# BLE-LORA-Relay-30dbm-v2_0.net
KiCad netlist of a schematic drawn in EAGLE
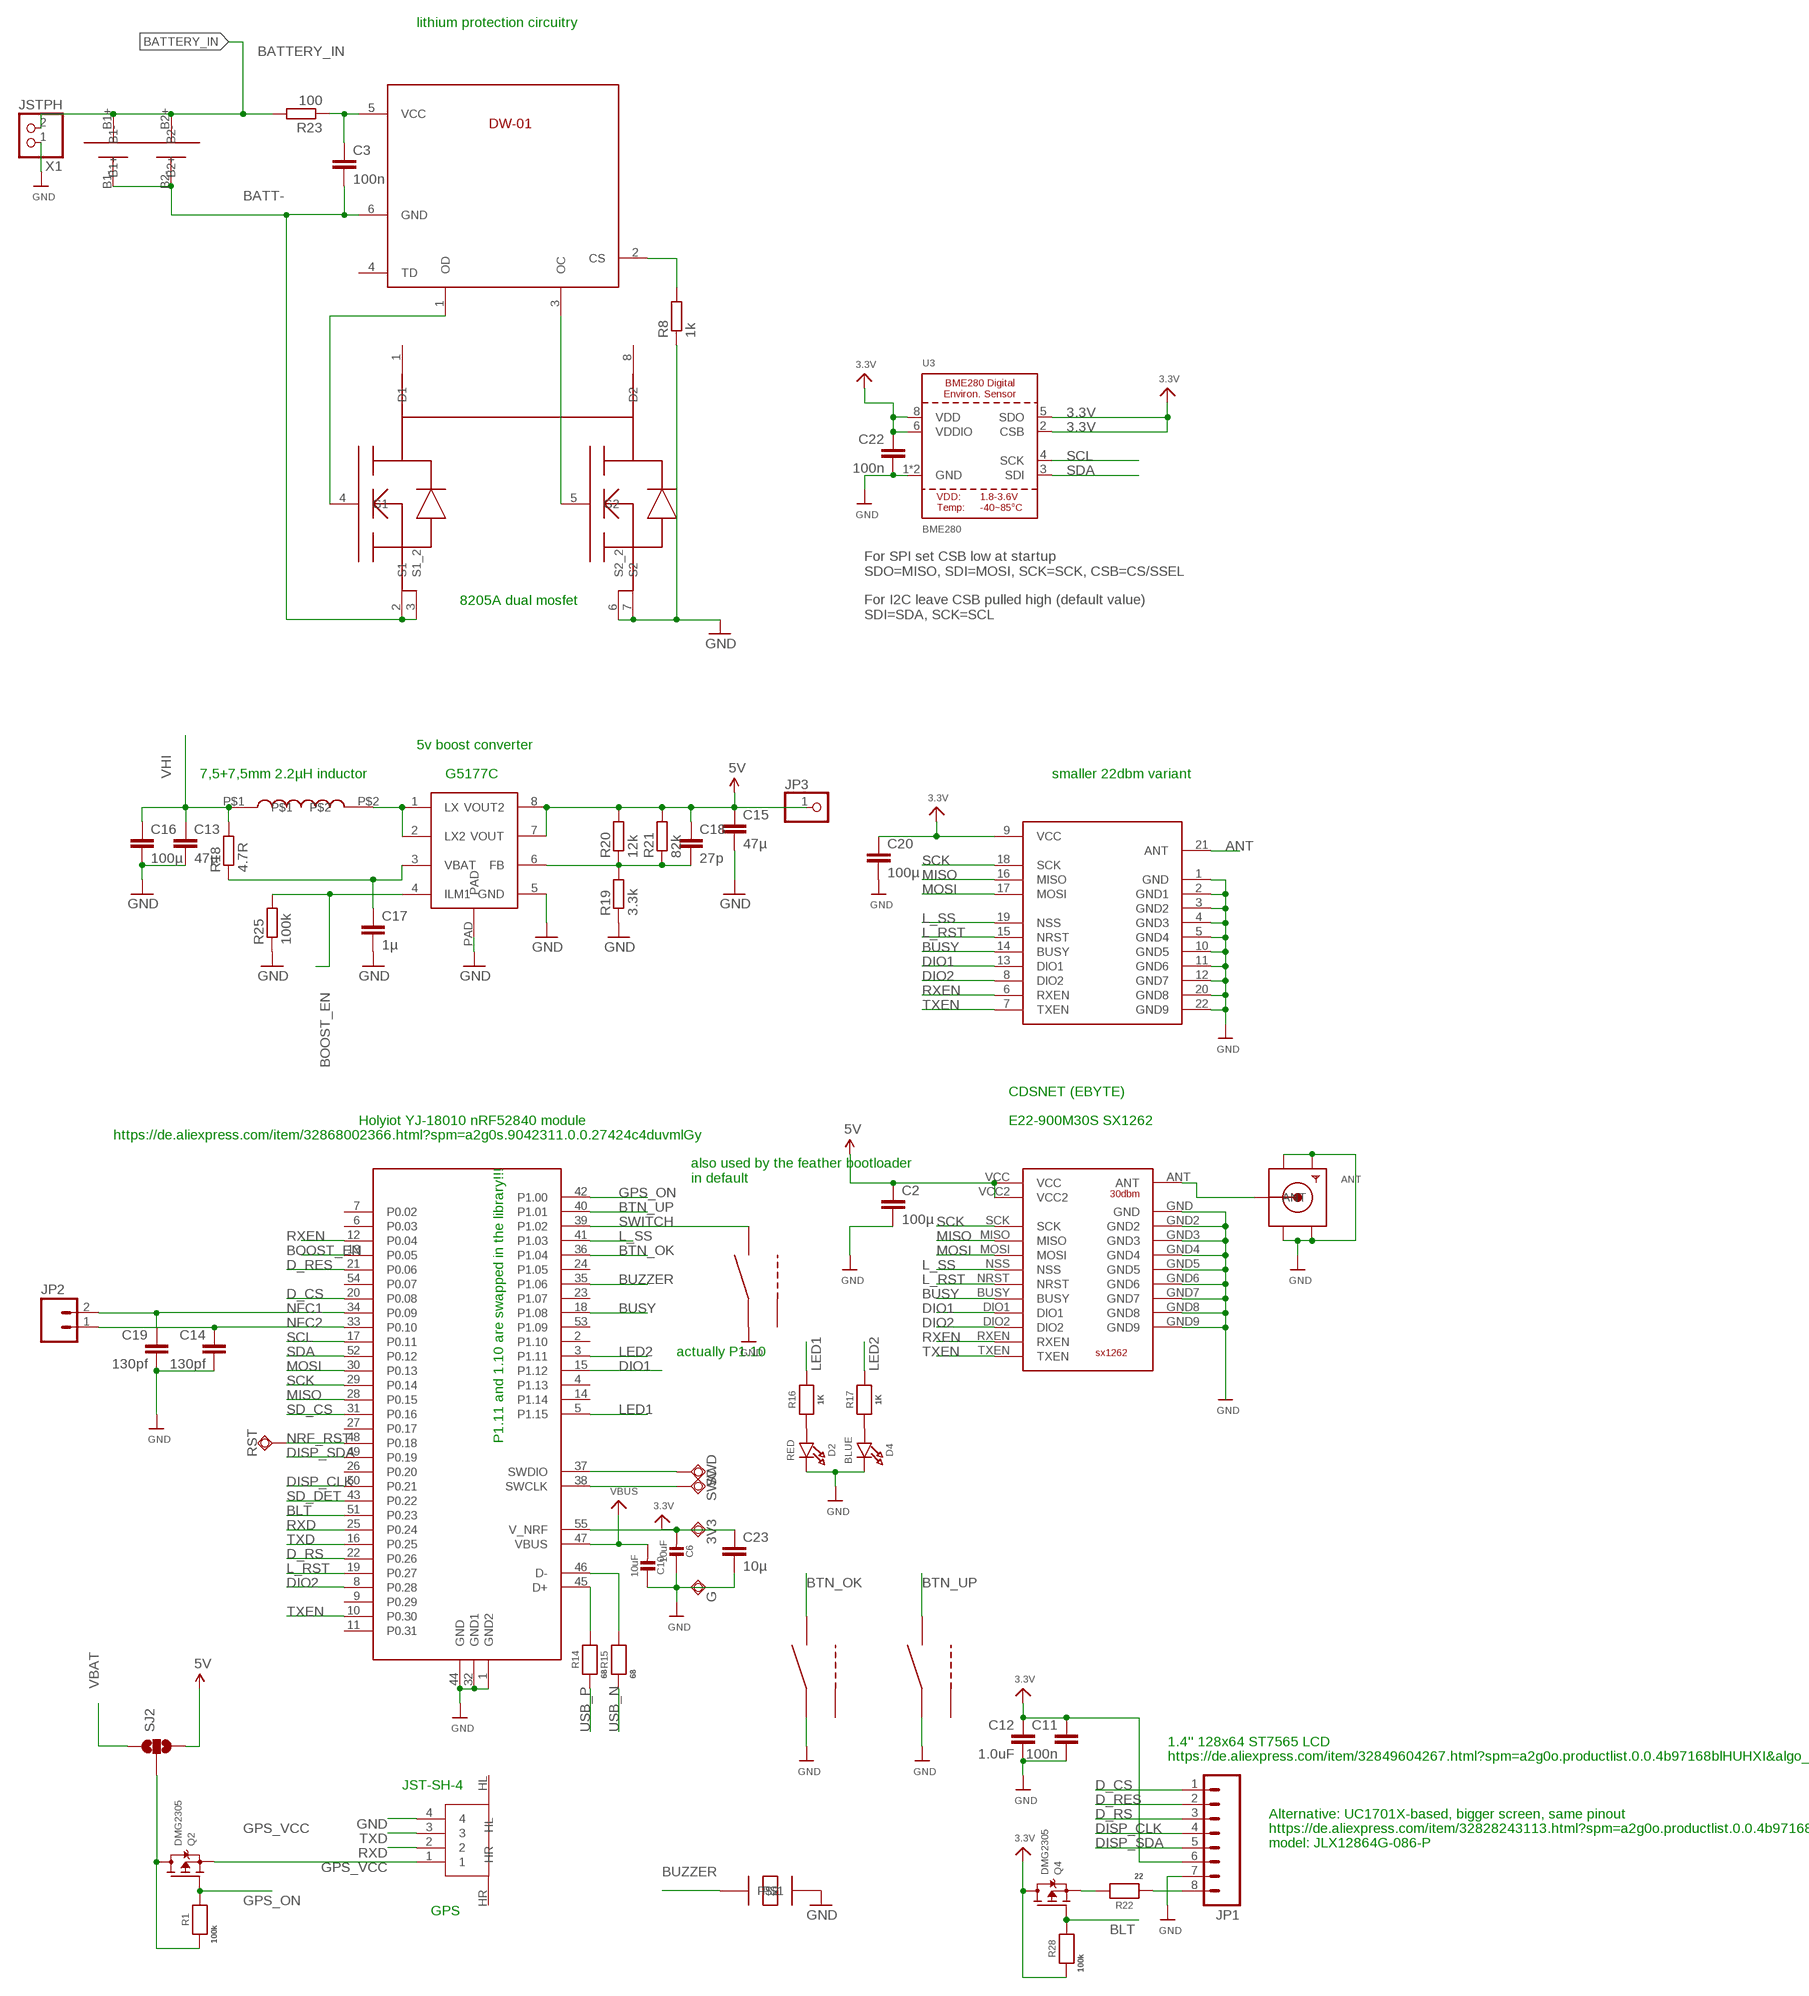
[diagram p0: schematic, sheet 1, part 1 of 3]
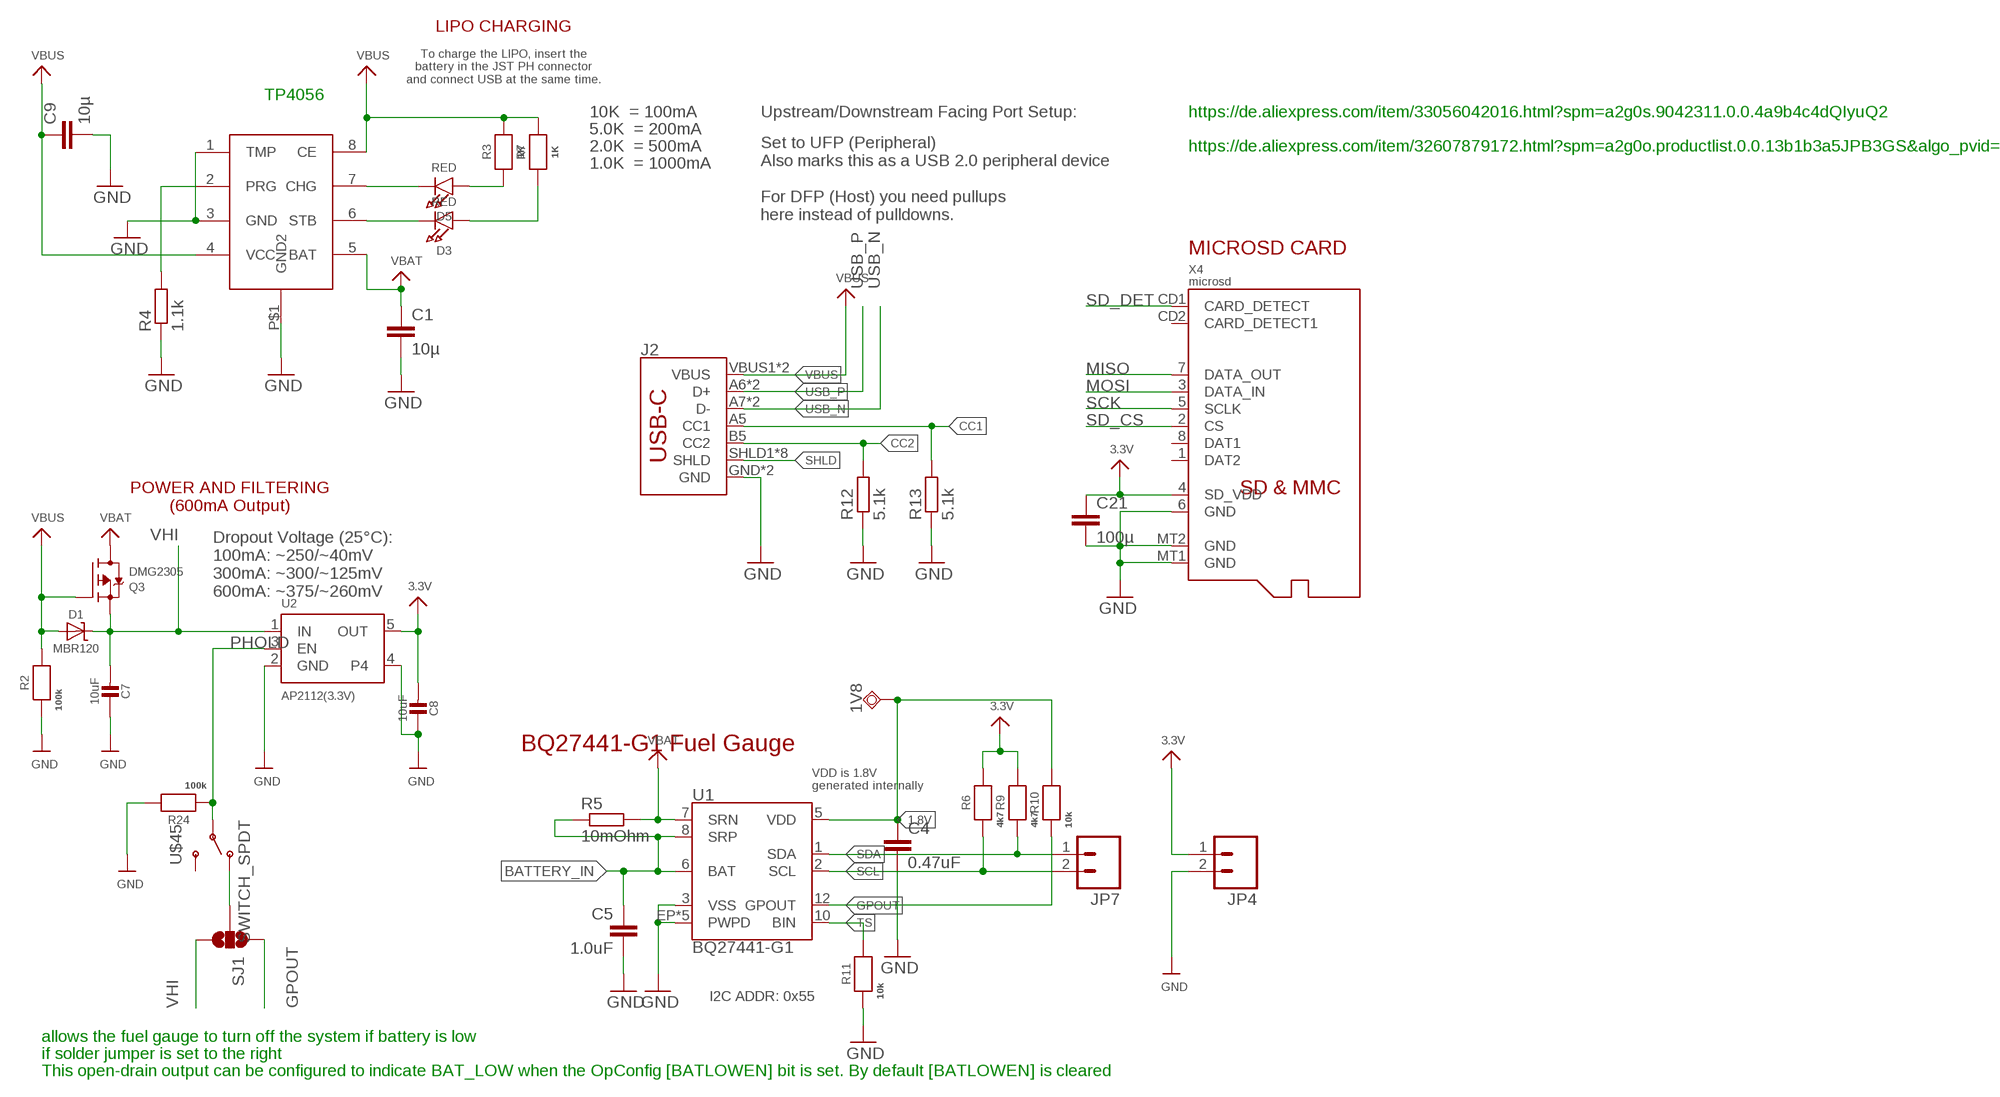
[diagram p1: schematic, sheet 1, part 2 of 3]
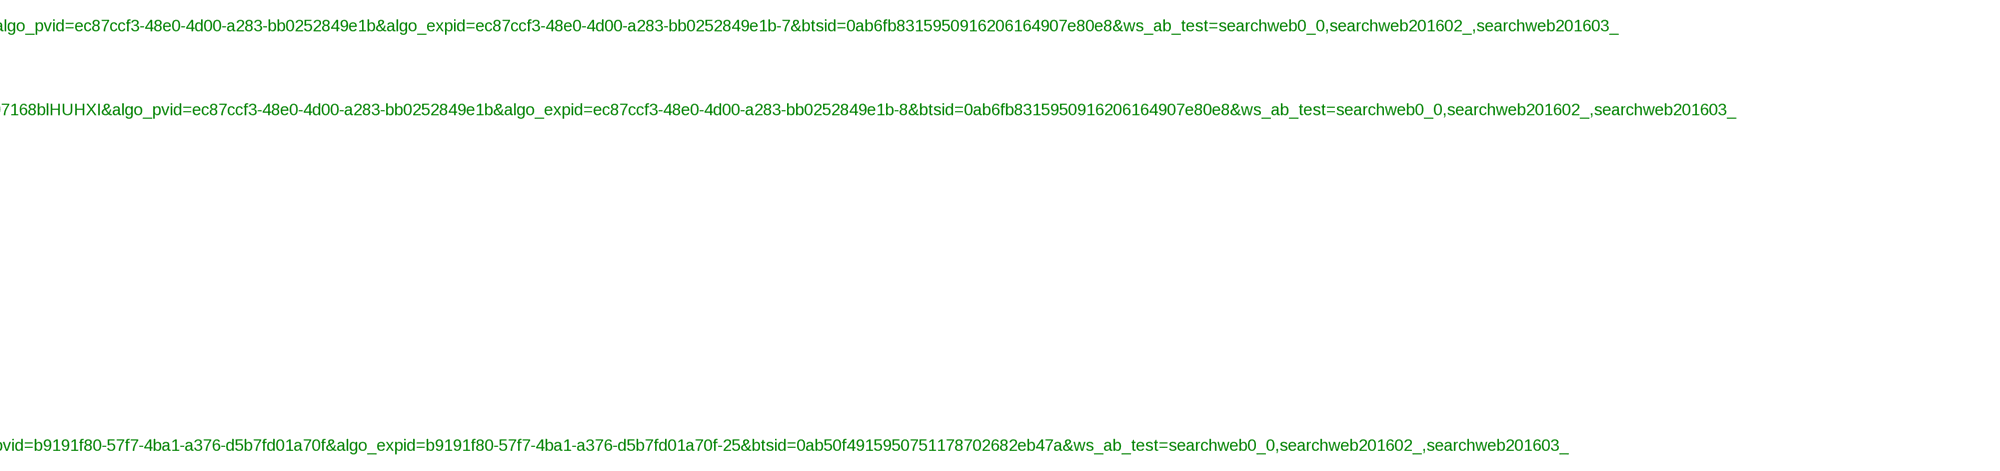
[diagram p2: schematic, sheet 1, part 3 of 3]

(export (version "E")
  (design (tool "Eeschema 10.0.6"))
  (components
    (comp (ref "1V8")
      (value "TPSQTP13R")
      (footprint "eagle-import:TP13R")
      (libsource (lib "eagle-import") (part "TPSQTP13R"))
    )
    (comp (ref "3V3")
      (value "TPSQTP13R")
      (footprint "eagle-import:TP13R")
      (libsource (lib "eagle-import") (part "TPSQTP13R"))
    )
    (comp (ref "ANT")
      (value "SMACONNECTOR_EDGE")
      (footprint "eagle-import:SMA_EDGELAUNCH")
      (libsource (lib "eagle-import") (part "SMACONNECTOR_EDGE"))
    )
    (comp (ref "C1")
      (value "10µ")
      (footprint "eagle-import:C0805")
      (libsource (lib "eagle-import") (part "C-EUC0805"))
    )
    (comp (ref "C2")
      (value "100µ")
      (footprint "eagle-import:C1206")
      (libsource (lib "eagle-import") (part "C-EUC1206"))
    )
    (comp (ref "C3")
      (value "100n")
      (footprint "eagle-import:C0603")
      (libsource (lib "eagle-import") (part "C-EUC0603"))
    )
    (comp (ref "C4")
      (value "0.47uF")
      (footprint "eagle-import:0603-CAP")
      (libsource (lib "eagle-import") (part "CAP0603-CAP"))
    )
    (comp (ref "C5")
      (value "1.0uF")
      (footprint "eagle-import:0603-CAP")
      (libsource (lib "eagle-import") (part "1.0UF-16V-10%(0603)"))
    )
    (comp (ref "C6")
      (value "10uF")
      (footprint "eagle-import:0805-NO")
      (libsource (lib "eagle-import") (part "CAP_CERAMIC0805-NOOUTLINE"))
    )
    (comp (ref "C7")
      (value "10uF")
      (footprint "eagle-import:0805-NO")
      (libsource (lib "eagle-import") (part "CAP_CERAMIC0805-NOOUTLINE"))
    )
    (comp (ref "C8")
      (value "10uF")
      (footprint "eagle-import:0805-NO")
      (libsource (lib "eagle-import") (part "CAP_CERAMIC0805-NOOUTLINE"))
    )
    (comp (ref "C9")
      (value "10µ")
      (footprint "eagle-import:C0805")
      (libsource (lib "eagle-import") (part "C-EUC0805"))
    )
    (comp (ref "C10")
      (value "10uF")
      (footprint "eagle-import:0805-NO")
      (libsource (lib "eagle-import") (part "CAP_CERAMIC0805-NOOUTLINE"))
    )
    (comp (ref "C11")
      (value "100n")
      (footprint "eagle-import:0603-CAP")
      (libsource (lib "eagle-import") (part "1.0UF-16V-10%(0603)"))
    )
    (comp (ref "C12")
      (value "1.0uF")
      (footprint "eagle-import:0603-CAP")
      (libsource (lib "eagle-import") (part "1.0UF-16V-10%(0603)"))
    )
    (comp (ref "C13")
      (value "47µ")
      (footprint "eagle-import:C0805")
      (libsource (lib "eagle-import") (part "C-EUC0805"))
    )
    (comp (ref "C14")
      (value "130pf")
      (footprint "eagle-import:0603-CAP")
      (libsource (lib "eagle-import") (part "1.0UF-16V-10%(0603)"))
    )
    (comp (ref "C15")
      (value "47µ")
      (footprint "eagle-import:C0805")
      (libsource (lib "eagle-import") (part "C-EUC0805"))
    )
    (comp (ref "C16")
      (value "100µ")
      (footprint "eagle-import:C1206")
      (libsource (lib "eagle-import") (part "C-EUC1206"))
    )
    (comp (ref "C17")
      (value "1µ")
      (footprint "eagle-import:C0603")
      (libsource (lib "eagle-import") (part "C-EUC0603"))
    )
    (comp (ref "C18")
      (value "27p")
      (footprint "eagle-import:C0603")
      (libsource (lib "eagle-import") (part "C-EUC0603"))
    )
    (comp (ref "C19")
      (value "130pf")
      (footprint "eagle-import:0603-CAP")
      (libsource (lib "eagle-import") (part "1.0UF-16V-10%(0603)"))
    )
    (comp (ref "C20")
      (value "100µ")
      (footprint "eagle-import:C1206")
      (libsource (lib "eagle-import") (part "C-EUC1206"))
    )
    (comp (ref "C21")
      (value "100µ")
      (footprint "eagle-import:C1206")
      (libsource (lib "eagle-import") (part "C-EUC1206"))
    )
    (comp (ref "C22")
      (value "100n")
      (footprint "eagle-import:0603-CAP")
      (libsource (lib "eagle-import") (part "1.0UF-16V-10%(0603)"))
    )
    (comp (ref "C23")
      (value "10µ")
      (footprint "eagle-import:C0805")
      (libsource (lib "eagle-import") (part "C-EUC0805"))
    )
    (comp (ref "D1")
      (value "MBR120")
      (footprint "eagle-import:SOD-123")
      (libsource (lib "eagle-import") (part "DIODE-SCHOTTKYSOD-123"))
    )
    (comp (ref "D2")
      (value "RED")
      (footprint "eagle-import:CHIPLED_0805_NOOUTLINE")
      (libsource (lib "eagle-import") (part "LED0805_NOOUTLINE"))
    )
    (comp (ref "D3")
      (value "RED")
      (footprint "eagle-import:CHIPLED_0805_NOOUTLINE")
      (libsource (lib "eagle-import") (part "LED0805_NOOUTLINE"))
    )
    (comp (ref "D4")
      (value "BLUE")
      (footprint "eagle-import:CHIPLED_0805_NOOUTLINE")
      (libsource (lib "eagle-import") (part "LED0805_NOOUTLINE"))
    )
    (comp (ref "D5")
      (value "RED")
      (footprint "eagle-import:CHIPLED_0805_NOOUTLINE")
      (libsource (lib "eagle-import") (part "LED0805_NOOUTLINE"))
    )
    (comp (ref "DWN")
      (value "LS12T2")
      (footprint "eagle-import:LS12T2")
      (libsource (lib "eagle-import") (part "LS12T2"))
    )
    (comp (ref "DWN1")
      (value "LS12T2")
      (footprint "eagle-import:LS12T2")
      (libsource (lib "eagle-import") (part "LS12T2"))
    )
    (comp (ref "DWN2")
      (value "LS12T2")
      (footprint "eagle-import:LS12T2")
      (libsource (lib "eagle-import") (part "LS12T2"))
    )
    (comp (ref "G")
      (value "TPSQTP13R")
      (footprint "eagle-import:TP13R")
      (libsource (lib "eagle-import") (part "TPSQTP13R"))
    )
    (comp (ref "J2")
      (value "USB_C16PIN")
      (footprint "eagle-import:USB-C-16P")
      (libsource (lib "eagle-import") (part "USB_C16PIN"))
    )
    (comp (ref "JP1")
      (value "M08")
      (footprint "eagle-import:1X08_ROUND")
      (libsource (lib "eagle-import") (part "M08"))
    )
    (comp (ref "JP2")
      (value "M02PTH")
      (footprint "eagle-import:1X02")
      (libsource (lib "eagle-import") (part "M02PTH"))
    )
    (comp (ref "JP3")
      (value "PINHD-1X1")
      (footprint "eagle-import:1X01")
      (libsource (lib "eagle-import") (part "PINHD-1X1"))
    )
    (comp (ref "JP4")
      (value "M02PTH")
      (footprint "eagle-import:1X02")
      (libsource (lib "eagle-import") (part "M02PTH"))
    )
    (comp (ref "JP7")
      (value "M02PTH")
      (footprint "eagle-import:1X02")
      (libsource (lib "eagle-import") (part "M02PTH"))
    )
    (comp (ref "Q2")
      (value "DMG2305")
      (footprint "eagle-import:SOT23-R")
      (libsource (lib "eagle-import") (part "MOSFET-P"))
    )
    (comp (ref "Q3")
      (value "DMG2305")
      (footprint "eagle-import:SOT23-R")
      (libsource (lib "eagle-import") (part "MOSFET-P"))
    )
    (comp (ref "Q4")
      (value "DMG2305")
      (footprint "eagle-import:SOT23-R")
      (libsource (lib "eagle-import") (part "MOSFET-P"))
    )
    (comp (ref "R1")
      (value "100k")
      (footprint "eagle-import:0603-NO")
      (libsource (lib "eagle-import") (part "RESISTOR_0603_NOOUT"))
    )
    (comp (ref "R2")
      (value "100k")
      (footprint "eagle-import:0603-NO")
      (libsource (lib "eagle-import") (part "RESISTOR_0603_NOOUT"))
    )
    (comp (ref "R3")
      (value "1K")
      (footprint "eagle-import:0603-NO")
      (libsource (lib "eagle-import") (part "RESISTOR_0603_NOOUT"))
    )
    (comp (ref "R4")
      (value "1.1k")
      (footprint "eagle-import:R0603")
      (libsource (lib "eagle-import") (part "R-EU_R0603"))
    )
    (comp (ref "R5")
      (value "10mOhm")
      (footprint "eagle-import:R0805")
      (libsource (lib "eagle-import") (part "R-EU_R0805"))
    )
    (comp (ref "R6")
      (value "4k7")
      (footprint "eagle-import:0603-NO")
      (libsource (lib "eagle-import") (part "RESISTOR_0603_NOOUT"))
    )
    (comp (ref "R7")
      (value "1K")
      (footprint "eagle-import:0603-NO")
      (libsource (lib "eagle-import") (part "RESISTOR_0603_NOOUT"))
    )
    (comp (ref "R8")
      (value "1k")
      (footprint "eagle-import:R0603")
      (libsource (lib "eagle-import") (part "R-EU_R0603"))
    )
    (comp (ref "R9")
      (value "4k7")
      (footprint "eagle-import:0603-NO")
      (libsource (lib "eagle-import") (part "RESISTOR_0603_NOOUT"))
    )
    (comp (ref "R10")
      (value "10k")
      (footprint "eagle-import:0603-NO")
      (libsource (lib "eagle-import") (part "RESISTOR_0603_NOOUT"))
    )
    (comp (ref "R11")
      (value "10k")
      (footprint "eagle-import:0603-NO")
      (libsource (lib "eagle-import") (part "RESISTOR_0603_NOOUT"))
    )
    (comp (ref "R12")
      (value "5.1k")
      (footprint "eagle-import:R0603")
      (libsource (lib "eagle-import") (part "R-EU_R0603"))
    )
    (comp (ref "R13")
      (value "5.1k")
      (footprint "eagle-import:R0603")
      (libsource (lib "eagle-import") (part "R-EU_R0603"))
    )
    (comp (ref "R14")
      (value "68")
      (footprint "eagle-import:0603-NO")
      (libsource (lib "eagle-import") (part "RESISTOR_0603_NOOUT"))
    )
    (comp (ref "R15")
      (value "68")
      (footprint "eagle-import:0603-NO")
      (libsource (lib "eagle-import") (part "RESISTOR_0603_NOOUT"))
    )
    (comp (ref "R16")
      (value "1K")
      (footprint "eagle-import:0603-NO")
      (libsource (lib "eagle-import") (part "RESISTOR_0603_NOOUT"))
    )
    (comp (ref "R17")
      (value "1K")
      (footprint "eagle-import:0603-NO")
      (libsource (lib "eagle-import") (part "RESISTOR_0603_NOOUT"))
    )
    (comp (ref "R18")
      (value "4.7R")
      (footprint "eagle-import:R0603")
      (libsource (lib "eagle-import") (part "R-EU_R0603"))
    )
    (comp (ref "R19")
      (value "3.3k")
      (footprint "eagle-import:R0603")
      (libsource (lib "eagle-import") (part "R-EU_R0603"))
    )
    (comp (ref "R20")
      (value "12k")
      (footprint "eagle-import:R0603")
      (libsource (lib "eagle-import") (part "R-EU_R0603"))
    )
    (comp (ref "R21")
      (value "82k")
      (footprint "eagle-import:R0603")
      (libsource (lib "eagle-import") (part "R-EU_R0603"))
    )
    (comp (ref "R22")
      (value "22")
      (footprint "eagle-import:0603-NO")
      (libsource (lib "eagle-import") (part "RESISTOR_0603_NOOUT"))
    )
    (comp (ref "R23")
      (value "100")
      (footprint "eagle-import:R0603")
      (libsource (lib "eagle-import") (part "R-EU_R0603"))
    )
    (comp (ref "R24")
      (value "100k")
      (footprint "eagle-import:0603-NO")
      (libsource (lib "eagle-import") (part "RESISTOR_0603_NOOUT"))
    )
    (comp (ref "R25")
      (value "100k")
      (footprint "eagle-import:R0603")
      (libsource (lib "eagle-import") (part "R-EU_R0603"))
    )
    (comp (ref "R28")
      (value "100k")
      (footprint "eagle-import:0603-NO")
      (libsource (lib "eagle-import") (part "RESISTOR_0603_NOOUT"))
    )
    (comp (ref "RST")
      (value "TPSQTP13R")
      (footprint "eagle-import:TP13R")
      (libsource (lib "eagle-import") (part "TPSQTP13R"))
    )
    (comp (ref "SJ1")
      (value "SOLDERJUMPER_2WAY-OLDS")
      (footprint "eagle-import:SJ_3")
      (libsource (lib "eagle-import") (part "SOLDERJUMPER_2WAY-OLDS"))
    )
    (comp (ref "SJ2")
      (value "SOLDERJUMPER_2WAY-OLDS")
      (footprint "eagle-import:SJ_3")
      (libsource (lib "eagle-import") (part "SOLDERJUMPER_2WAY-OLDS"))
    )
    (comp (ref "SWC")
      (value "TPSQTP13R")
      (footprint "eagle-import:TP13R")
      (libsource (lib "eagle-import") (part "TPSQTP13R"))
    )
    (comp (ref "SWD")
      (value "TPSQTP13R")
      (footprint "eagle-import:TP13R")
      (libsource (lib "eagle-import") (part "TPSQTP13R"))
    )
    (comp (ref "U$2")
      (value "BUZZER")
      (footprint "eagle-import:BUZZER")
      (libsource (lib "eagle-import") (part "BUZZER"))
    )
    (comp (ref "U$3")
      (value "TP4056")
      (footprint "eagle-import:SO-08")
      (libsource (lib "eagle-import") (part "TP4056"))
    )
    (comp (ref "U$10")
      (value "2X18650")
      (footprint "eagle-import:2X18650")
      (libsource (lib "eagle-import") (part "2X18650"))
    )
    (comp (ref "U$14")
      (value "NRF52840")
      (footprint "eagle-import:NRF52840MOD")
      (libsource (lib "eagle-import") (part "NRF52840"))
    )
    (comp (ref "U$15")
      (value "SX1262-30DBM")
      (footprint "eagle-import:SX1262-30DBM")
      (libsource (lib "eagle-import") (part "SX1262-30DBM"))
    )
    (comp (ref "U$17")
      (value "JST-SH-3")
      (footprint "eagle-import:JST-SH-3")
      (libsource (lib "eagle-import") (part "JST-SH-3"))
    )
    (comp (ref "U$35")
      (value "7.5MM-COIL")
      (footprint "eagle-import:7.5MM_COIL")
      (libsource (lib "eagle-import") (part "7.5MM-COIL"))
    )
    (comp (ref "U$36")
      (value "SX1292-EBYTE")
      (footprint "eagle-import:SX1262_EBYTE")
      (libsource (lib "eagle-import") (part "SX1292-EBYTE"))
    )
    (comp (ref "U$38")
      (value "DW-01")
      (footprint "eagle-import:SOT23-6")
      (libsource (lib "eagle-import") (part "DW-01"))
    )
    (comp (ref "U$41")
      (value "G5177C")
      (footprint "eagle-import:SO-08")
      (libsource (lib "eagle-import") (part "G5177C"))
    )
    (comp (ref "U$45")
      (value "SWITCH_SPDT")
      (footprint "eagle-import:KPS-1290")
      (libsource (lib "eagle-import") (part "SWITCH_SPDT"))
    )
    (comp (ref "U$46")
      (value "8205A")
      (footprint "eagle-import:TSSOP8")
      (libsource (lib "eagle-import") (part "8205A"))
    )
    (comp (ref "U1")
      (value "BQ27441-G1")
      (footprint "eagle-import:PDSO-N12")
      (libsource (lib "eagle-import") (part "BQ27441-G1"))
    )
    (comp (ref "U2")
      (value "AP2112(3.3V)")
      (footprint "eagle-import:SOT23-5")
      (libsource (lib "eagle-import") (part "VREG_SOT23-5"))
    )
    (comp (ref "U3")
      (value "BME280")
      (footprint "eagle-import:BME280")
      (libsource (lib "eagle-import") (part "BME280"))
    )
    (comp (ref "X1")
      (value "JSTPH")
      (footprint "eagle-import:JSTPH2")
      (libsource (lib "eagle-import") (part "CON_JST_PH_2PIN"))
    )
    (comp (ref "X4")
      (value "microsd")
      (footprint "eagle-import:MICROSD")
      (libsource (lib "eagle-import") (part "MICROSD"))
    )
  )
  (nets
    (net (code "1") (name "/ANT") (class "Default")
      (node (ref "ANT") (pin "P") (pinfunction "ANT_P") (pintype "bidirectional"))
      (node (ref "U$15") (pin "ANT") (pinfunction "ANT_ANT") (pintype "bidirectional"))
      (node (ref "U$36") (pin "21") (pinfunction "ANT_21") (pintype "bidirectional"))
    )
    (net (code "2") (name "/BATT-") (class "Default")
      (node (ref "C3") (pin "2") (pinfunction "2_2") (pintype "passive"))
      (node (ref "U$10") (pin "B1-") (pinfunction "B1-_B1-") (pintype "bidirectional"))
      (node (ref "U$10") (pin "B2-") (pinfunction "B2-_B2-") (pintype "bidirectional"))
      (node (ref "U$38") (pin "6") (pinfunction "GND_6") (pintype "bidirectional"))
      (node (ref "U$46") (pin "2") (pinfunction "S1_2") (pintype "bidirectional"))
      (node (ref "U$46") (pin "3") (pinfunction "S1_2_3") (pintype "bidirectional"))
    )
    (net (code "3") (name "/BLT") (class "Default")
      (node (ref "Q4") (pin "1") (pinfunction "G_1") (pintype "passive"))
      (node (ref "R28") (pin "2") (pinfunction "2_2") (pintype "passive"))
      (node (ref "U$14") (pin "51") (pinfunction "P0.23_51") (pintype "bidirectional"))
    )
    (net (code "4") (name "/BOOST_EN") (class "Default")
      (node (ref "R25") (pin "2") (pinfunction "2_2") (pintype "passive"))
      (node (ref "U$14") (pin "13") (pinfunction "P0.05_13") (pintype "bidirectional"))
      (node (ref "U$41") (pin "4") (pinfunction "ILM1_4") (pintype "bidirectional"))
    )
    (net (code "5") (name "/BTN_OK") (class "Default")
      (node (ref "DWN") (pin "1") (pinfunction "1_1") (pintype "bidirectional"))
      (node (ref "U$14") (pin "36") (pinfunction "P1.04_36") (pintype "bidirectional"))
    )
    (net (code "6") (name "/BTN_UP") (class "Default")
      (node (ref "DWN1") (pin "1") (pinfunction "1_1") (pintype "bidirectional"))
      (node (ref "U$14") (pin "40") (pinfunction "P1.01_40") (pintype "bidirectional"))
    )
    (net (code "7") (name "/BUSY") (class "Default")
      (node (ref "U$14") (pin "18") (pinfunction "P1.08_18") (pintype "bidirectional"))
      (node (ref "U$15") (pin "BUSY") (pinfunction "BUSY_BUSY") (pintype "bidirectional"))
      (node (ref "U$36") (pin "14") (pinfunction "BUSY_14") (pintype "bidirectional"))
    )
    (net (code "8") (name "/BUZZER") (class "Default")
      (node (ref "U$14") (pin "35") (pinfunction "P1.06_35") (pintype "bidirectional"))
      (node (ref "U$2") (pin "P$1") (pinfunction "P$1_P$1") (pintype "bidirectional"))
    )
    (net (code "9") (name "/DIO1") (class "Default")
      (node (ref "U$14") (pin "15") (pinfunction "P1.12_15") (pintype "bidirectional"))
      (node (ref "U$15") (pin "DIO1") (pinfunction "DIO1_DIO1") (pintype "bidirectional"))
      (node (ref "U$36") (pin "13") (pinfunction "DIO1_13") (pintype "bidirectional"))
    )
    (net (code "10") (name "/DIO2") (class "Default")
      (node (ref "U$14") (pin "8") (pinfunction "P0.28_8") (pintype "bidirectional"))
      (node (ref "U$15") (pin "DIO2") (pinfunction "DIO2_DIO2") (pintype "bidirectional"))
      (node (ref "U$36") (pin "8") (pinfunction "DIO2_8") (pintype "bidirectional"))
    )
    (net (code "11") (name "/DISP_CLK") (class "Default")
      (node (ref "JP1") (pin "4") (pinfunction "4_4") (pintype "passive"))
      (node (ref "U$14") (pin "50") (pinfunction "P0.21_50") (pintype "bidirectional"))
    )
    (net (code "12") (name "/DISP_SDA") (class "Default")
      (node (ref "JP1") (pin "5") (pinfunction "5_5") (pintype "passive"))
      (node (ref "U$14") (pin "49") (pinfunction "P0.19_49") (pintype "bidirectional"))
    )
    (net (code "13") (name "/D_CS") (class "Default")
      (node (ref "JP1") (pin "1") (pinfunction "1_1") (pintype "passive"))
      (node (ref "U$14") (pin "20") (pinfunction "P0.08_20") (pintype "bidirectional"))
    )
    (net (code "14") (name "/D_RES") (class "Default")
      (node (ref "JP1") (pin "2") (pinfunction "2_2") (pintype "passive"))
      (node (ref "U$14") (pin "21") (pinfunction "P0.06_21") (pintype "bidirectional"))
    )
    (net (code "15") (name "/D_RS") (class "Default")
      (node (ref "JP1") (pin "3") (pinfunction "3_3") (pintype "passive"))
      (node (ref "U$14") (pin "22") (pinfunction "P0.26_22") (pintype "bidirectional"))
    )
    (net (code "16") (name "/GPS_ON") (class "Default")
      (node (ref "Q2") (pin "1") (pinfunction "G_1") (pintype "passive"))
      (node (ref "R1") (pin "2") (pinfunction "2_2") (pintype "passive"))
      (node (ref "U$14") (pin "42") (pinfunction "P1.00_42") (pintype "bidirectional"))
    )
    (net (code "17") (name "/GPS_VCC") (class "Default")
      (node (ref "Q2") (pin "2") (pinfunction "S_2") (pintype "passive"))
      (node (ref "U$17") (pin "1") (pinfunction "1_1") (pintype "bidirectional"))
    )
    (net (code "18") (name "/LED1") (class "Default")
      (node (ref "R16") (pin "2") (pinfunction "2_2") (pintype "passive"))
      (node (ref "U$14") (pin "5") (pinfunction "P1.15_5") (pintype "bidirectional"))
    )
    (net (code "19") (name "/LED2") (class "Default")
      (node (ref "R17") (pin "2") (pinfunction "2_2") (pintype "passive"))
      (node (ref "U$14") (pin "3") (pinfunction "P1.11_3") (pintype "bidirectional"))
    )
    (net (code "20") (name "/L_RST") (class "Default")
      (node (ref "U$14") (pin "19") (pinfunction "P0.27_19") (pintype "bidirectional"))
      (node (ref "U$15") (pin "NRST") (pinfunction "NRST_NRST") (pintype "bidirectional"))
      (node (ref "U$36") (pin "15") (pinfunction "NRST_15") (pintype "bidirectional"))
    )
    (net (code "21") (name "/L_SS") (class "Default")
      (node (ref "U$14") (pin "41") (pinfunction "P1.03_41") (pintype "bidirectional"))
      (node (ref "U$15") (pin "NSS") (pinfunction "NSS_NSS") (pintype "bidirectional"))
      (node (ref "U$36") (pin "19") (pinfunction "NSS_19") (pintype "bidirectional"))
    )
    (net (code "22") (name "/MISO") (class "Default")
      (node (ref "U$14") (pin "28") (pinfunction "P0.15_28") (pintype "bidirectional"))
      (node (ref "U$15") (pin "MISO") (pinfunction "MISO_MISO") (pintype "bidirectional"))
      (node (ref "U$36") (pin "16") (pinfunction "MISO_16") (pintype "bidirectional"))
      (node (ref "X4") (pin "7") (pinfunction "DATA_OUT_7") (pintype "output"))
    )
    (net (code "23") (name "/MOSI") (class "Default")
      (node (ref "U$14") (pin "30") (pinfunction "P0.13_30") (pintype "bidirectional"))
      (node (ref "U$15") (pin "MOSI") (pinfunction "MOSI_MOSI") (pintype "bidirectional"))
      (node (ref "U$36") (pin "17") (pinfunction "MOSI_17") (pintype "bidirectional"))
      (node (ref "X4") (pin "3") (pinfunction "DATA_IN_3") (pintype "input"))
    )
    (net (code "24") (name "/NFC1") (class "Default")
      (node (ref "C19") (pin "1") (pinfunction "1_1") (pintype "passive"))
      (node (ref "JP2") (pin "2") (pinfunction "2_2") (pintype "passive"))
      (node (ref "U$14") (pin "34") (pinfunction "P0.09_34") (pintype "bidirectional"))
    )
    (net (code "25") (name "/NFC2") (class "Default")
      (node (ref "C14") (pin "1") (pinfunction "1_1") (pintype "passive"))
      (node (ref "JP2") (pin "1") (pinfunction "1_1") (pintype "passive"))
      (node (ref "U$14") (pin "33") (pinfunction "P0.10_33") (pintype "bidirectional"))
    )
    (net (code "26") (name "/NRF_RST") (class "Default")
      (node (ref "RST") (pin "TP") (pinfunction "TP_TP") (pintype "input"))
      (node (ref "U$14") (pin "48") (pinfunction "P0.18_48") (pintype "bidirectional"))
    )
    (net (code "27") (name "/PHOLD") (class "Default")
      (node (ref "R24") (pin "1") (pinfunction "1_1") (pintype "passive"))
      (node (ref "U$45") (pin "P") (pinfunction "P_P") (pintype "passive"))
      (node (ref "U2") (pin "3") (pinfunction "EN_3") (pintype "input"))
    )
    (net (code "28") (name "/RXD") (class "Default")
      (node (ref "U$14") (pin "25") (pinfunction "P0.24_25") (pintype "bidirectional"))
      (node (ref "U$17") (pin "2") (pinfunction "2_2") (pintype "bidirectional"))
    )
    (net (code "29") (name "/RXEN") (class "Default")
      (node (ref "U$14") (pin "12") (pinfunction "P0.04_12") (pintype "bidirectional"))
      (node (ref "U$15") (pin "RXEN") (pinfunction "RXEN_RXEN") (pintype "bidirectional"))
      (node (ref "U$36") (pin "6") (pinfunction "RXEN_6") (pintype "bidirectional"))
    )
    (net (code "30") (name "/SCK") (class "Default")
      (node (ref "U$14") (pin "29") (pinfunction "P0.14_29") (pintype "bidirectional"))
      (node (ref "U$15") (pin "SCK") (pinfunction "SCK_SCK") (pintype "bidirectional"))
      (node (ref "U$36") (pin "18") (pinfunction "SCK_18") (pintype "bidirectional"))
      (node (ref "X4") (pin "5") (pinfunction "SCLK_5") (pintype "input"))
    )
    (net (code "31") (name "/SD_CS") (class "Default")
      (node (ref "U$14") (pin "31") (pinfunction "P0.16_31") (pintype "bidirectional"))
      (node (ref "X4") (pin "2") (pinfunction "CS_2") (pintype "input"))
    )
    (net (code "32") (name "/SD_DET") (class "Default")
      (node (ref "U$14") (pin "43") (pinfunction "P0.22_43") (pintype "bidirectional"))
      (node (ref "X4") (pin "CD1") (pinfunction "CARD_DETECT_CD1") (pintype "passive"))
    )
    (net (code "33") (name "/SWITCH") (class "Default")
      (node (ref "DWN2") (pin "1") (pinfunction "1_1") (pintype "bidirectional"))
      (node (ref "U$14") (pin "39") (pinfunction "P1.02_39") (pintype "bidirectional"))
    )
    (net (code "34") (name "/TXD") (class "Default")
      (node (ref "U$14") (pin "16") (pinfunction "P0.25_16") (pintype "bidirectional"))
      (node (ref "U$17") (pin "3") (pinfunction "3_3") (pintype "bidirectional"))
    )
    (net (code "35") (name "/TXEN") (class "Default")
      (node (ref "U$14") (pin "10") (pinfunction "P0.30_10") (pintype "bidirectional"))
      (node (ref "U$15") (pin "TXEN") (pinfunction "TXEN_TXEN") (pintype "bidirectional"))
      (node (ref "U$36") (pin "7") (pinfunction "TXEN_7") (pintype "bidirectional"))
    )
    (net (code "36") (name "/VHI") (class "Default")
      (node (ref "C13") (pin "1") (pinfunction "1_1") (pintype "passive"))
      (node (ref "C16") (pin "1") (pinfunction "1_1") (pintype "passive"))
      (node (ref "C7") (pin "2") (pinfunction "2_2") (pintype "passive"))
      (node (ref "D1") (pin "C") (pinfunction "C_C") (pintype "passive"))
      (node (ref "Q3") (pin "2") (pinfunction "S_2") (pintype "passive"))
      (node (ref "R18") (pin "2") (pinfunction "2_2") (pintype "passive"))
      (node (ref "SJ1") (pin "3") (pinfunction "3_3") (pintype "passive"))
      (node (ref "U$35") (pin "P$1") (pinfunction "P$1_P$1") (pintype "bidirectional"))
      (node (ref "U2") (pin "1") (pinfunction "IN_1") (pintype "power_in"))
    )
    (net (code "37") (name "1.8V") (class "Default")
      (node (ref "1V8") (pin "TP") (pinfunction "TP_TP") (pintype "input"))
      (node (ref "C4") (pin "1") (pinfunction "1_1") (pintype "passive"))
      (node (ref "R10") (pin "2") (pinfunction "2_2") (pintype "passive"))
      (node (ref "U1") (pin "5") (pinfunction "VDD_5") (pintype "bidirectional"))
    )
    (net (code "38") (name "3.3V") (class "Default")
      (node (ref "3V3") (pin "TP") (pinfunction "TP_TP") (pintype "input"))
      (node (ref "C11") (pin "1") (pinfunction "1_1") (pintype "passive"))
      (node (ref "C12") (pin "1") (pinfunction "1_1") (pintype "passive"))
      (node (ref "C20") (pin "1") (pinfunction "1_1") (pintype "passive"))
      (node (ref "C21") (pin "1") (pinfunction "1_1") (pintype "passive"))
      (node (ref "C22") (pin "1") (pinfunction "1_1") (pintype "passive"))
      (node (ref "C23") (pin "1") (pinfunction "1_1") (pintype "passive"))
      (node (ref "C6") (pin "2") (pinfunction "2_2") (pintype "passive"))
      (node (ref "C8") (pin "2") (pinfunction "2_2") (pintype "passive"))
      (node (ref "JP1") (pin "6") (pinfunction "6_6") (pintype "passive"))
      (node (ref "JP4") (pin "1") (pinfunction "1_1") (pintype "passive"))
      (node (ref "Q4") (pin "3") (pinfunction "D_3") (pintype "passive"))
      (node (ref "R28") (pin "1") (pinfunction "1_1") (pintype "passive"))
      (node (ref "R6") (pin "2") (pinfunction "2_2") (pintype "passive"))
      (node (ref "R9") (pin "2") (pinfunction "2_2") (pintype "passive"))
      (node (ref "U$14") (pin "55") (pinfunction "V_NRF_55") (pintype "bidirectional"))
      (node (ref "U$36") (pin "9") (pinfunction "VCC_9") (pintype "bidirectional"))
      (node (ref "U2") (pin "5") (pinfunction "OUT_5") (pintype "power_in"))
      (node (ref "U3") (pin "2") (pinfunction "CSB_2") (pintype "input"))
      (node (ref "U3") (pin "5") (pinfunction "SDO_5") (pintype "output"))
      (node (ref "U3") (pin "6") (pinfunction "VDDIO_6") (pintype "power_in"))
      (node (ref "U3") (pin "8") (pinfunction "VDD_8") (pintype "power_in"))
      (node (ref "X4") (pin "4") (pinfunction "SD_VDD_4") (pintype "power_in"))
    )
    (net (code "39") (name "5V") (class "Default")
      (node (ref "C15") (pin "1") (pinfunction "1_1") (pintype "passive"))
      (node (ref "C18") (pin "1") (pinfunction "1_1") (pintype "passive"))
      (node (ref "C2") (pin "1") (pinfunction "1_1") (pintype "passive"))
      (node (ref "JP3") (pin "1") (pinfunction "1_1") (pintype "passive"))
      (node (ref "R20") (pin "2") (pinfunction "2_2") (pintype "passive"))
      (node (ref "R21") (pin "2") (pinfunction "2_2") (pintype "passive"))
      (node (ref "SJ2") (pin "3") (pinfunction "3_3") (pintype "passive"))
      (node (ref "U$15") (pin "VCC") (pinfunction "VCC_VCC") (pintype "bidirectional"))
      (node (ref "U$15") (pin "VCC2") (pinfunction "VCC2_VCC2") (pintype "bidirectional"))
      (node (ref "U$41") (pin "7") (pinfunction "VOUT_7") (pintype "bidirectional"))
      (node (ref "U$41") (pin "8") (pinfunction "VOUT2_8") (pintype "bidirectional"))
    )
    (net (code "40") (name "BATTERY_IN") (class "Default")
      (node (ref "C5") (pin "1") (pinfunction "1_1") (pintype "passive"))
      (node (ref "R23") (pin "2") (pinfunction "2_2") (pintype "passive"))
      (node (ref "R5") (pin "1") (pinfunction "1_1") (pintype "passive"))
      (node (ref "U$10") (pin "B1+") (pinfunction "B1+_B1+") (pintype "bidirectional"))
      (node (ref "U$10") (pin "B2+") (pinfunction "B2+_B2+") (pintype "bidirectional"))
      (node (ref "U1") (pin "6") (pinfunction "BAT_6") (pintype "bidirectional"))
      (node (ref "U1") (pin "8") (pinfunction "SRP_8") (pintype "bidirectional"))
      (node (ref "X1") (pin "2") (pinfunction "2_2") (pintype "passive"))
    )
    (net (code "41") (name "CC1") (class "Default")
      (node (ref "J2") (pin "A5") (pinfunction "CC1_A5") (pintype "bidirectional"))
      (node (ref "R13") (pin "2") (pinfunction "2_2") (pintype "passive"))
    )
    (net (code "42") (name "CC2") (class "Default")
      (node (ref "J2") (pin "B5") (pinfunction "CC2_B5") (pintype "bidirectional"))
      (node (ref "R12") (pin "2") (pinfunction "2_2") (pintype "passive"))
    )
    (net (code "43") (name "GND") (class "Default")
      (node (ref "ANT") (pin "GND@1") (pinfunction "GND4_GND@1") (pintype "power_in"))
      (node (ref "ANT") (pin "GND@2") (pinfunction "GND3_GND@2") (pintype "power_in"))
      (node (ref "ANT") (pin "GND@3") (pinfunction "GND2_GND@3") (pintype "power_in"))
      (node (ref "ANT") (pin "GND@4") (pinfunction "GND1_GND@4") (pintype "power_in"))
      (node (ref "C1") (pin "2") (pinfunction "2_2") (pintype "passive"))
      (node (ref "C10") (pin "1") (pinfunction "1_1") (pintype "passive"))
      (node (ref "C11") (pin "2") (pinfunction "2_2") (pintype "passive"))
      (node (ref "C12") (pin "2") (pinfunction "2_2") (pintype "passive"))
      (node (ref "C13") (pin "2") (pinfunction "2_2") (pintype "passive"))
      (node (ref "C14") (pin "2") (pinfunction "2_2") (pintype "passive"))
      (node (ref "C15") (pin "2") (pinfunction "2_2") (pintype "passive"))
      (node (ref "C16") (pin "2") (pinfunction "2_2") (pintype "passive"))
      (node (ref "C17") (pin "2") (pinfunction "2_2") (pintype "passive"))
      (node (ref "C19") (pin "2") (pinfunction "2_2") (pintype "passive"))
      (node (ref "C2") (pin "2") (pinfunction "2_2") (pintype "passive"))
      (node (ref "C20") (pin "2") (pinfunction "2_2") (pintype "passive"))
      (node (ref "C21") (pin "2") (pinfunction "2_2") (pintype "passive"))
      (node (ref "C22") (pin "2") (pinfunction "2_2") (pintype "passive"))
      (node (ref "C23") (pin "2") (pinfunction "2_2") (pintype "passive"))
      (node (ref "C4") (pin "2") (pinfunction "2_2") (pintype "passive"))
      (node (ref "C5") (pin "2") (pinfunction "2_2") (pintype "passive"))
      (node (ref "C6") (pin "1") (pinfunction "1_1") (pintype "passive"))
      (node (ref "C7") (pin "1") (pinfunction "1_1") (pintype "passive"))
      (node (ref "C8") (pin "1") (pinfunction "1_1") (pintype "passive"))
      (node (ref "C9") (pin "2") (pinfunction "2_2") (pintype "passive"))
      (node (ref "D2") (pin "C") (pinfunction "C_C") (pintype "passive"))
      (node (ref "D4") (pin "C") (pinfunction "C_C") (pintype "passive"))
      (node (ref "DWN") (pin "2") (pinfunction "2_2") (pintype "bidirectional"))
      (node (ref "DWN1") (pin "2") (pinfunction "2_2") (pintype "bidirectional"))
      (node (ref "DWN2") (pin "2") (pinfunction "2_2") (pintype "bidirectional"))
      (node (ref "G") (pin "TP") (pinfunction "TP_TP") (pintype "input"))
      (node (ref "J2") (pin "GND") (pinfunction "GND_GND") (pintype "bidirectional"))
      (node (ref "J2") (pin "GND2") (pinfunction "GND_GND2") (pintype "bidirectional"))
      (node (ref "JP1") (pin "7") (pinfunction "7_7") (pintype "passive"))
      (node (ref "JP4") (pin "2") (pinfunction "2_2") (pintype "passive"))
      (node (ref "R11") (pin "1") (pinfunction "1_1") (pintype "passive"))
      (node (ref "R12") (pin "1") (pinfunction "1_1") (pintype "passive"))
      (node (ref "R13") (pin "1") (pinfunction "1_1") (pintype "passive"))
      (node (ref "R19") (pin "1") (pinfunction "1_1") (pintype "passive"))
      (node (ref "R2") (pin "1") (pinfunction "1_1") (pintype "passive"))
      (node (ref "R24") (pin "2") (pinfunction "2_2") (pintype "passive"))
      (node (ref "R25") (pin "1") (pinfunction "1_1") (pintype "passive"))
      (node (ref "R4") (pin "1") (pinfunction "1_1") (pintype "passive"))
      (node (ref "R8") (pin "1") (pinfunction "1_1") (pintype "passive"))
      (node (ref "U$14") (pin "1") (pinfunction "GND2_1") (pintype "bidirectional"))
      (node (ref "U$14") (pin "32") (pinfunction "GND1_32") (pintype "bidirectional"))
      (node (ref "U$14") (pin "44") (pinfunction "GND_44") (pintype "bidirectional"))
      (node (ref "U$15") (pin "GND") (pinfunction "GND_GND") (pintype "bidirectional"))
      (node (ref "U$15") (pin "GND2") (pinfunction "GND2_GND2") (pintype "bidirectional"))
      (node (ref "U$15") (pin "GND3") (pinfunction "GND3_GND3") (pintype "bidirectional"))
      (node (ref "U$15") (pin "GND4") (pinfunction "GND4_GND4") (pintype "bidirectional"))
      (node (ref "U$15") (pin "GND5") (pinfunction "GND5_GND5") (pintype "bidirectional"))
      (node (ref "U$15") (pin "GND6") (pinfunction "GND6_GND6") (pintype "bidirectional"))
      (node (ref "U$15") (pin "GND7") (pinfunction "GND7_GND7") (pintype "bidirectional"))
      (node (ref "U$15") (pin "GND8") (pinfunction "GND8_GND8") (pintype "bidirectional"))
      (node (ref "U$15") (pin "GND9") (pinfunction "GND9_GND9") (pintype "bidirectional"))
      (node (ref "U$17") (pin "4") (pinfunction "4_4") (pintype "bidirectional"))
      (node (ref "U$2") (pin "P$2") (pinfunction "P$2_P$2") (pintype "bidirectional"))
      (node (ref "U$3") (pin "1") (pinfunction "TMP_1") (pintype "bidirectional"))
      (node (ref "U$3") (pin "3") (pinfunction "GND_3") (pintype "bidirectional"))
      (node (ref "U$3") (pin "P$1") (pinfunction "GND2_P$1") (pintype "bidirectional"))
      (node (ref "U$36") (pin "1") (pinfunction "GND_1") (pintype "bidirectional"))
      (node (ref "U$36") (pin "10") (pinfunction "GND5_10") (pintype "bidirectional"))
      (node (ref "U$36") (pin "11") (pinfunction "GND6_11") (pintype "bidirectional"))
      (node (ref "U$36") (pin "12") (pinfunction "GND7_12") (pintype "bidirectional"))
      (node (ref "U$36") (pin "2") (pinfunction "GND1_2") (pintype "bidirectional"))
      (node (ref "U$36") (pin "20") (pinfunction "GND8_20") (pintype "bidirectional"))
      (node (ref "U$36") (pin "22") (pinfunction "GND9_22") (pintype "bidirectional"))
      (node (ref "U$36") (pin "3") (pinfunction "GND2_3") (pintype "bidirectional"))
      (node (ref "U$36") (pin "4") (pinfunction "GND3_4") (pintype "bidirectional"))
      (node (ref "U$36") (pin "5") (pinfunction "GND4_5") (pintype "bidirectional"))
      (node (ref "U$41") (pin "5") (pinfunction "GND_5") (pintype "bidirectional"))
      (node (ref "U$41") (pin "PAD") (pinfunction "PAD_PAD") (pintype "bidirectional"))
      (node (ref "U$46") (pin "6") (pinfunction "S2_2_6") (pintype "bidirectional"))
      (node (ref "U$46") (pin "7") (pinfunction "S2_7") (pintype "bidirectional"))
      (node (ref "U1") (pin "3") (pinfunction "VSS_3") (pintype "bidirectional"))
      (node (ref "U1") (pin "EP") (pinfunction "PWPD_EP") (pintype "bidirectional"))
      (node (ref "U1") (pin "EP1") (pinfunction "PWPD_EP1") (pintype "bidirectional"))
      (node (ref "U1") (pin "EP2") (pinfunction "PWPD_EP2") (pintype "bidirectional"))
      (node (ref "U1") (pin "EP3") (pinfunction "PWPD_EP3") (pintype "bidirectional"))
      (node (ref "U1") (pin "EP4") (pinfunction "PWPD_EP4") (pintype "bidirectional"))
      (node (ref "U2") (pin "2") (pinfunction "GND_2") (pintype "power_in"))
      (node (ref "U2") (pin "4") (pinfunction "P4_4") (pintype "bidirectional"))
      (node (ref "U3") (pin "1") (pinfunction "GND_1") (pintype "power_in"))
      (node (ref "U3") (pin "7") (pinfunction "GND_7") (pintype "power_in"))
      (node (ref "X1") (pin "1") (pinfunction "1_1") (pintype "passive"))
      (node (ref "X4") (pin "6") (pinfunction "GND_6") (pintype "power_in"))
      (node (ref "X4") (pin "MT1") (pinfunction "GND_MT1") (pintype "power_in"))
      (node (ref "X4") (pin "MT2") (pinfunction "GND_MT2") (pintype "power_in"))
    )
    (net (code "44") (name "GPOUT") (class "Default")
      (node (ref "R10") (pin "1") (pinfunction "1_1") (pintype "passive"))
      (node (ref "SJ1") (pin "1") (pinfunction "1_1") (pintype "passive"))
      (node (ref "U1") (pin "12") (pinfunction "GPOUT_12") (pintype "bidirectional"))
    )
    (net (code "45") (name "Net-(D2-PadA)") (class "Default")
      (node (ref "D2") (pin "A") (pinfunction "A_A") (pintype "passive"))
      (node (ref "R16") (pin "1") (pinfunction "1_1") (pintype "passive"))
    )
    (net (code "46") (name "Net-(D3-PadA)") (class "Default")
      (node (ref "D3") (pin "A") (pinfunction "A_A") (pintype "passive"))
      (node (ref "R7") (pin "1") (pinfunction "1_1") (pintype "passive"))
    )
    (net (code "47") (name "Net-(D4-PadA)") (class "Default")
      (node (ref "D4") (pin "A") (pinfunction "A_A") (pintype "passive"))
      (node (ref "R17") (pin "1") (pinfunction "1_1") (pintype "passive"))
    )
    (net (code "48") (name "Net-(D5-PadA)") (class "Default")
      (node (ref "D5") (pin "A") (pinfunction "A_A") (pintype "passive"))
      (node (ref "R3") (pin "1") (pinfunction "1_1") (pintype "passive"))
    )
    (net (code "49") (name "Net-(JP1-Pad8)") (class "Default")
      (node (ref "JP1") (pin "8") (pinfunction "8_8") (pintype "passive"))
      (node (ref "R22") (pin "1") (pinfunction "1_1") (pintype "passive"))
    )
    (net (code "50") (name "Net-(Q2-D)") (class "Default")
      (node (ref "Q2") (pin "3") (pinfunction "D_3") (pintype "passive"))
      (node (ref "R1") (pin "1") (pinfunction "1_1") (pintype "passive"))
      (node (ref "SJ2") (pin "2") (pinfunction "2_2") (pintype "passive"))
    )
    (net (code "51") (name "Net-(Q4-S)") (class "Default")
      (node (ref "Q4") (pin "2") (pinfunction "S_2") (pintype "passive"))
      (node (ref "R22") (pin "2") (pinfunction "2_2") (pintype "passive"))
    )
    (net (code "52") (name "Net-(SJ1-Pad2)") (class "Default")
      (node (ref "SJ1") (pin "2") (pinfunction "2_2") (pintype "passive"))
      (node (ref "U$45") (pin "O") (pinfunction "O_O") (pintype "passive"))
    )
    (net (code "53") (name "Net-(U$3-CHG)") (class "Default")
      (node (ref "D5") (pin "C") (pinfunction "C_C") (pintype "passive"))
      (node (ref "U$3") (pin "7") (pinfunction "CHG_7") (pintype "bidirectional"))
    )
    (net (code "54") (name "Net-(U$3-PRG)") (class "Default")
      (node (ref "R4") (pin "2") (pinfunction "2_2") (pintype "passive"))
      (node (ref "U$3") (pin "2") (pinfunction "PRG_2") (pintype "bidirectional"))
    )
    (net (code "55") (name "Net-(U$3-STB)") (class "Default")
      (node (ref "D3") (pin "C") (pinfunction "C_C") (pintype "passive"))
      (node (ref "U$3") (pin "6") (pinfunction "STB_6") (pintype "bidirectional"))
    )
    (net (code "56") (name "Net-(U$14-D+)") (class "Default")
      (node (ref "R14") (pin "2") (pinfunction "2_2") (pintype "passive"))
      (node (ref "U$14") (pin "45") (pinfunction "D+_45") (pintype "bidirectional"))
    )
    (net (code "57") (name "Net-(U$14-D-)") (class "Default")
      (node (ref "R15") (pin "2") (pinfunction "2_2") (pintype "passive"))
      (node (ref "U$14") (pin "46") (pinfunction "D-_46") (pintype "bidirectional"))
    )
    (net (code "58") (name "Net-(U$14-SWCLK)") (class "Default")
      (node (ref "SWC") (pin "TP") (pinfunction "TP_TP") (pintype "input"))
      (node (ref "U$14") (pin "38") (pinfunction "SWCLK_38") (pintype "bidirectional"))
    )
    (net (code "59") (name "Net-(U$14-SWDIO)") (class "Default")
      (node (ref "SWD") (pin "TP") (pinfunction "TP_TP") (pintype "input"))
      (node (ref "U$14") (pin "37") (pinfunction "SWDIO_37") (pintype "bidirectional"))
    )
    (net (code "60") (name "Net-(U$38-CS)") (class "Default")
      (node (ref "R8") (pin "2") (pinfunction "2_2") (pintype "passive"))
      (node (ref "U$38") (pin "2") (pinfunction "CS_2") (pintype "bidirectional"))
    )
    (net (code "61") (name "Net-(U$38-OC)") (class "Default")
      (node (ref "U$38") (pin "3") (pinfunction "OC_3") (pintype "bidirectional"))
      (node (ref "U$46") (pin "5") (pinfunction "G2_5") (pintype "bidirectional"))
    )
    (net (code "62") (name "Net-(U$38-OD)") (class "Default")
      (node (ref "U$38") (pin "1") (pinfunction "OD_1") (pintype "bidirectional"))
      (node (ref "U$46") (pin "4") (pinfunction "G1_4") (pintype "bidirectional"))
    )
    (net (code "63") (name "Net-(U$38-VCC)") (class "Default")
      (node (ref "C3") (pin "1") (pinfunction "1_1") (pintype "passive"))
      (node (ref "R23") (pin "1") (pinfunction "1_1") (pintype "passive"))
      (node (ref "U$38") (pin "5") (pinfunction "VCC_5") (pintype "bidirectional"))
    )
    (net (code "64") (name "Net-(U$41-FB)") (class "Default")
      (node (ref "C18") (pin "2") (pinfunction "2_2") (pintype "passive"))
      (node (ref "R19") (pin "2") (pinfunction "2_2") (pintype "passive"))
      (node (ref "R20") (pin "1") (pinfunction "1_1") (pintype "passive"))
      (node (ref "R21") (pin "1") (pinfunction "1_1") (pintype "passive"))
      (node (ref "U$41") (pin "6") (pinfunction "FB_6") (pintype "bidirectional"))
    )
    (net (code "65") (name "Net-(U$41-LX)") (class "Default")
      (node (ref "U$35") (pin "P$2") (pinfunction "P$2_P$2") (pintype "bidirectional"))
      (node (ref "U$41") (pin "1") (pinfunction "LX_1") (pintype "bidirectional"))
      (node (ref "U$41") (pin "2") (pinfunction "LX2_2") (pintype "bidirectional"))
    )
    (net (code "66") (name "Net-(U$41-VBAT)") (class "Default")
      (node (ref "C17") (pin "1") (pinfunction "1_1") (pintype "passive"))
      (node (ref "R18") (pin "1") (pinfunction "1_1") (pintype "passive"))
      (node (ref "U$41") (pin "3") (pinfunction "VBAT_3") (pintype "bidirectional"))
    )
    (net (code "67") (name "SCL") (class "Default")
      (node (ref "JP7") (pin "2") (pinfunction "2_2") (pintype "passive"))
      (node (ref "R6") (pin "1") (pinfunction "1_1") (pintype "passive"))
      (node (ref "U$14") (pin "17") (pinfunction "P0.11_17") (pintype "bidirectional"))
      (node (ref "U1") (pin "2") (pinfunction "SCL_2") (pintype "bidirectional"))
      (node (ref "U3") (pin "4") (pinfunction "SCK_4") (pintype "input"))
    )
    (net (code "68") (name "SDA") (class "Default")
      (node (ref "JP7") (pin "1") (pinfunction "1_1") (pintype "passive"))
      (node (ref "R9") (pin "1") (pinfunction "1_1") (pintype "passive"))
      (node (ref "U$14") (pin "52") (pinfunction "P0.12_52") (pintype "bidirectional"))
      (node (ref "U1") (pin "1") (pinfunction "SDA_1") (pintype "bidirectional"))
      (node (ref "U3") (pin "3") (pinfunction "SDI_3") (pintype "input"))
    )
    (net (code "69") (name "SHLD") (class "Default")
      (node (ref "J2") (pin "SHLD1") (pinfunction "SHLD_SHLD1") (pintype "bidirectional"))
      (node (ref "J2") (pin "SHLD2") (pinfunction "SHLD_SHLD2") (pintype "bidirectional"))
      (node (ref "J2") (pin "SHLD3") (pinfunction "SHLD_SHLD3") (pintype "bidirectional"))
      (node (ref "J2") (pin "SHLD4") (pinfunction "SHLD_SHLD4") (pintype "bidirectional"))
      (node (ref "J2") (pin "SHLD5") (pinfunction "SHLD_SHLD5") (pintype "bidirectional"))
      (node (ref "J2") (pin "SHLD6") (pinfunction "SHLD_SHLD6") (pintype "bidirectional"))
      (node (ref "J2") (pin "SHLD7") (pinfunction "SHLD_SHLD7") (pintype "bidirectional"))
      (node (ref "J2") (pin "SHLD8") (pinfunction "SHLD_SHLD8") (pintype "bidirectional"))
    )
    (net (code "70") (name "TS") (class "Default")
      (node (ref "R11") (pin "2") (pinfunction "2_2") (pintype "passive"))
      (node (ref "U1") (pin "10") (pinfunction "BIN_10") (pintype "bidirectional"))
    )
    (net (code "71") (name "USB_N") (class "Default")
      (node (ref "J2") (pin "A7") (pinfunction "D-_A7") (pintype "bidirectional"))
      (node (ref "J2") (pin "B7") (pinfunction "D-_B7") (pintype "bidirectional"))
      (node (ref "R15") (pin "1") (pinfunction "1_1") (pintype "passive"))
    )
    (net (code "72") (name "USB_P") (class "Default")
      (node (ref "J2") (pin "A6") (pinfunction "D+_A6") (pintype "bidirectional"))
      (node (ref "J2") (pin "B6") (pinfunction "D+_B6") (pintype "bidirectional"))
      (node (ref "R14") (pin "1") (pinfunction "1_1") (pintype "passive"))
    )
    (net (code "73") (name "VBAT") (class "Default")
      (node (ref "C1") (pin "1") (pinfunction "1_1") (pintype "passive"))
      (node (ref "Q3") (pin "3") (pinfunction "D_3") (pintype "passive"))
      (node (ref "R5") (pin "2") (pinfunction "2_2") (pintype "passive"))
      (node (ref "SJ2") (pin "1") (pinfunction "1_1") (pintype "passive"))
      (node (ref "U$3") (pin "5") (pinfunction "BAT_5") (pintype "bidirectional"))
      (node (ref "U1") (pin "7") (pinfunction "SRN_7") (pintype "bidirectional"))
    )
    (net (code "74") (name "VBUS") (class "Default")
      (node (ref "C10") (pin "2") (pinfunction "2_2") (pintype "passive"))
      (node (ref "C9") (pin "1") (pinfunction "1_1") (pintype "passive"))
      (node (ref "D1") (pin "A") (pinfunction "A_A") (pintype "passive"))
      (node (ref "J2") (pin "VBUS1") (pinfunction "VBUS_VBUS1") (pintype "bidirectional"))
      (node (ref "J2") (pin "VBUS2") (pinfunction "VBUS_VBUS2") (pintype "bidirectional"))
      (node (ref "Q3") (pin "1") (pinfunction "G_1") (pintype "passive"))
      (node (ref "R2") (pin "2") (pinfunction "2_2") (pintype "passive"))
      (node (ref "R3") (pin "2") (pinfunction "2_2") (pintype "passive"))
      (node (ref "R7") (pin "2") (pinfunction "2_2") (pintype "passive"))
      (node (ref "U$14") (pin "47") (pinfunction "VBUS_47") (pintype "bidirectional"))
      (node (ref "U$3") (pin "4") (pinfunction "VCC_4") (pintype "bidirectional"))
      (node (ref "U$3") (pin "8") (pinfunction "CE_8") (pintype "bidirectional"))
    )
    (net (code "75") (name "unconnected-(DWN-FRM-PadFRAME)") (class "Default")
      (node (ref "DWN") (pin "FRAME") (pinfunction "FRM_FRAME") (pintype "bidirectional"))
    )
    (net (code "76") (name "unconnected-(DWN1-FRM-PadFRAME)") (class "Default")
      (node (ref "DWN1") (pin "FRAME") (pinfunction "FRM_FRAME") (pintype "bidirectional"))
    )
    (net (code "77") (name "unconnected-(DWN2-FRM-PadFRAME)") (class "Default")
      (node (ref "DWN2") (pin "FRAME") (pinfunction "FRM_FRAME") (pintype "bidirectional"))
    )
    (net (code "78") (name "unconnected-(U$14-P0.02-Pad7)") (class "Default")
      (node (ref "U$14") (pin "7") (pinfunction "P0.02_7") (pintype "bidirectional"))
    )
    (net (code "79") (name "unconnected-(U$14-P0.03-Pad6)") (class "Default")
      (node (ref "U$14") (pin "6") (pinfunction "P0.03_6") (pintype "bidirectional"))
    )
    (net (code "80") (name "unconnected-(U$14-P0.07-Pad54)") (class "Default")
      (node (ref "U$14") (pin "54") (pinfunction "P0.07_54") (pintype "bidirectional"))
    )
    (net (code "81") (name "unconnected-(U$14-P0.17-Pad27)") (class "Default")
      (node (ref "U$14") (pin "27") (pinfunction "P0.17_27") (pintype "bidirectional"))
    )
    (net (code "82") (name "unconnected-(U$14-P0.20-Pad26)") (class "Default")
      (node (ref "U$14") (pin "26") (pinfunction "P0.20_26") (pintype "bidirectional"))
    )
    (net (code "83") (name "unconnected-(U$14-P0.29-Pad9)") (class "Default")
      (node (ref "U$14") (pin "9") (pinfunction "P0.29_9") (pintype "bidirectional"))
    )
    (net (code "84") (name "unconnected-(U$14-P0.31-Pad11)") (class "Default")
      (node (ref "U$14") (pin "11") (pinfunction "P0.31_11") (pintype "bidirectional"))
    )
    (net (code "85") (name "unconnected-(U$14-P1.05-Pad24)") (class "Default")
      (node (ref "U$14") (pin "24") (pinfunction "P1.05_24") (pintype "bidirectional"))
    )
    (net (code "86") (name "unconnected-(U$14-P1.07-Pad23)") (class "Default")
      (node (ref "U$14") (pin "23") (pinfunction "P1.07_23") (pintype "bidirectional"))
    )
    (net (code "87") (name "unconnected-(U$14-P1.09-Pad53)") (class "Default")
      (node (ref "U$14") (pin "53") (pinfunction "P1.09_53") (pintype "bidirectional"))
    )
    (net (code "88") (name "unconnected-(U$14-P1.10-Pad2)") (class "Default")
      (node (ref "U$14") (pin "2") (pinfunction "P1.10_2") (pintype "bidirectional"))
    )
    (net (code "89") (name "unconnected-(U$14-P1.13-Pad4)") (class "Default")
      (node (ref "U$14") (pin "4") (pinfunction "P1.13_4") (pintype "bidirectional"))
    )
    (net (code "90") (name "unconnected-(U$14-P1.14-Pad14)") (class "Default")
      (node (ref "U$14") (pin "14") (pinfunction "P1.14_14") (pintype "bidirectional"))
    )
    (net (code "91") (name "unconnected-(U$17-PadHL)") (class "Default")
      (node (ref "U$17") (pin "HL") (pinfunction "HL_HL") (pintype "bidirectional"))
    )
    (net (code "92") (name "unconnected-(U$17-PadHR)") (class "Default")
      (node (ref "U$17") (pin "HR") (pinfunction "HR_HR") (pintype "bidirectional"))
    )
    (net (code "93") (name "unconnected-(U$38-TD-Pad4)") (class "Default")
      (node (ref "U$38") (pin "4") (pinfunction "TD_4") (pintype "bidirectional"))
    )
    (net (code "94") (name "unconnected-(U$45-PadS)") (class "Default")
      (node (ref "U$45") (pin "S") (pinfunction "S_S") (pintype "passive"))
    )
    (net (code "95") (name "unconnected-(U$46-D1-Pad1)") (class "Default")
      (node (ref "U$46") (pin "1") (pinfunction "D1_1") (pintype "bidirectional"))
    )
    (net (code "96") (name "unconnected-(U$46-D2-Pad8)") (class "Default")
      (node (ref "U$46") (pin "8") (pinfunction "D2_8") (pintype "bidirectional"))
    )
    (net (code "97") (name "unconnected-(X4-CARD_DETECT1-PadCD2)") (class "Default")
      (node (ref "X4") (pin "CD2") (pinfunction "CARD_DETECT1_CD2") (pintype "passive"))
    )
    (net (code "98") (name "unconnected-(X4-DAT1-Pad8)") (class "Default")
      (node (ref "X4") (pin "8") (pinfunction "DAT1_8") (pintype "bidirectional"))
    )
    (net (code "99") (name "unconnected-(X4-DAT2-Pad1)") (class "Default")
      (node (ref "X4") (pin "1") (pinfunction "DAT2_1") (pintype "bidirectional"))
    )
  )
)
